# akabeacon_mini_MDBT40.net
KiCad netlist of a schematic drawn in EAGLE
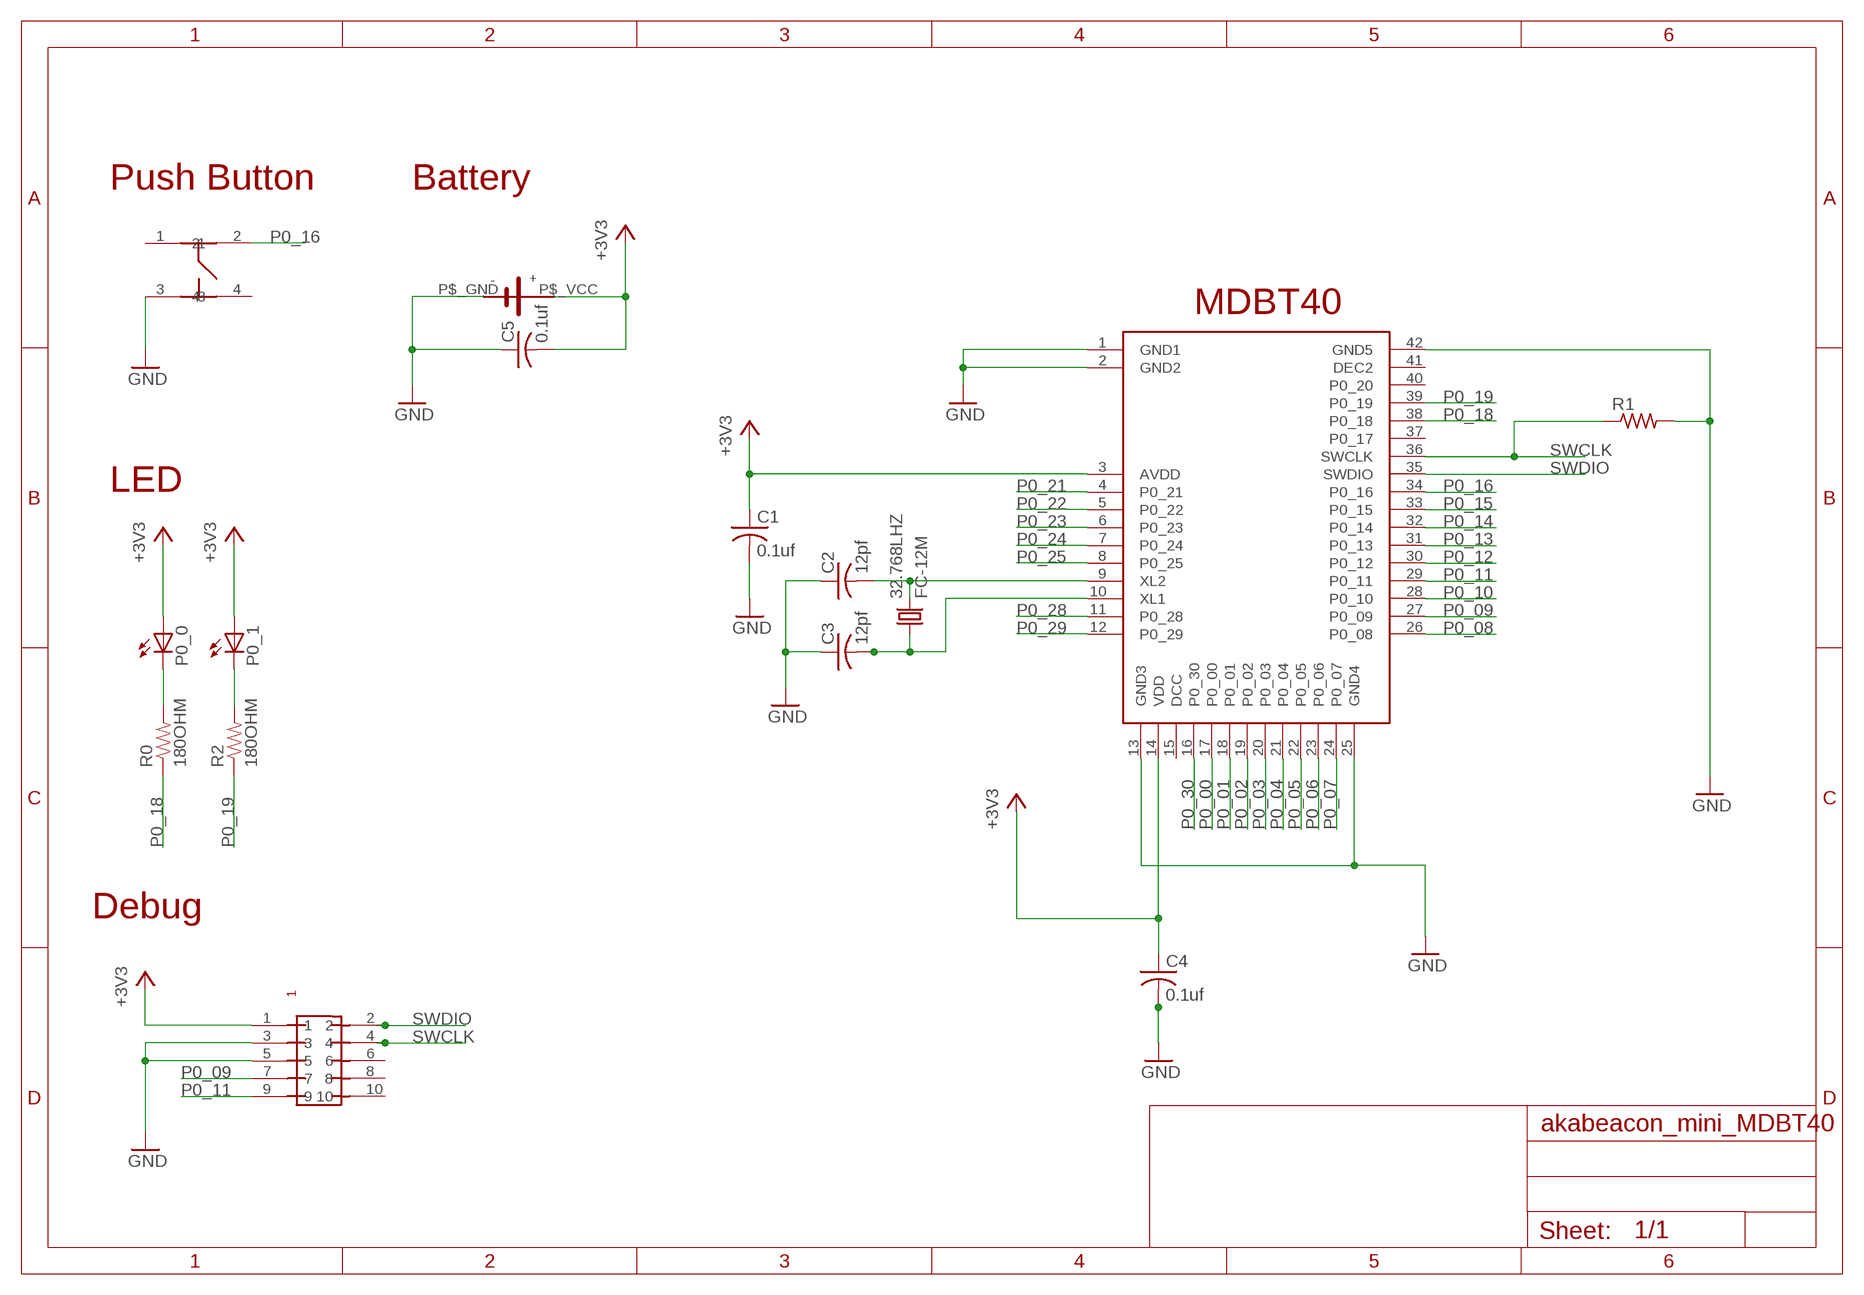
[diagram p0: schematic, sheet 1]

(export (version "E")
  (design (tool "Eeschema 10.0.6"))
  (components
    (comp (ref "32.768LHZ")
      (value "FC-12M")
      (footprint "eagle-import:FC-12M")
      (libsource (lib "eagle-import") (part "FC-12M"))
    )
    (comp (ref "C1")
      (value "0.1uf")
      (footprint "eagle-import:C0603")
      (libsource (lib "eagle-import") (part "C-USC0603"))
    )
    (comp (ref "C2")
      (value "12pf")
      (footprint "eagle-import:C0603")
      (libsource (lib "eagle-import") (part "C-USC0603"))
    )
    (comp (ref "C3")
      (value "12pf")
      (footprint "eagle-import:C0603")
      (libsource (lib "eagle-import") (part "C-USC0603"))
    )
    (comp (ref "C4")
      (value "0.1uf")
      (footprint "eagle-import:C0603")
      (libsource (lib "eagle-import") (part "C-USC0603"))
    )
    (comp (ref "C5")
      (value "0.1uf")
      (footprint "eagle-import:C0603")
      (libsource (lib "eagle-import") (part "C-USC0603"))
    )
    (comp (ref "P0_0")
      (value "LEDCHIP-LED0603")
      (footprint "eagle-import:CHIP-LED0603")
      (libsource (lib "eagle-import") (part "LEDCHIP-LED0603"))
    )
    (comp (ref "P0_1")
      (value "LEDCHIP-LED0603")
      (footprint "eagle-import:CHIP-LED0603")
      (libsource (lib "eagle-import") (part "LEDCHIP-LED0603"))
    )
    (comp (ref "R0")
      (value "180OHM")
      (footprint "eagle-import:0603-RES")
      (libsource (lib "eagle-import") (part "RESISTOR0603-RES"))
    )
    (comp (ref "R1")
      (value "R-US_R0603")
      (footprint "eagle-import:R0603")
      (libsource (lib "eagle-import") (part "R-US_R0603"))
    )
    (comp (ref "R2")
      (value "180OHM")
      (footprint "eagle-import:0603-RES")
      (libsource (lib "eagle-import") (part "RESISTOR0603-RES"))
    )
    (comp (ref "U$1")
      (value "RAYTAC-MDBT40")
      (footprint "eagle-import:RAYTAC-MDBT40")
      (libsource (lib "eagle-import") (part "RAYTAC-MDBT40"))
    )
    (comp (ref "U$2")
      (value "PIN-HEADER-SMT(1.27MM)2X5")
      (footprint "eagle-import:PIN-HEADER-SMT(1.27MM)2X5")
      (libsource (lib "eagle-import") (part "PIN-HEADER-SMT(1.27MM)2X5"))
    )
    (comp (ref "U$3")
      (value "SMTU2450-BOTTOM-MINI")
      (footprint "eagle-import:SMTU2450-BOTTOM-MINI")
      (libsource (lib "eagle-import") (part "SMTU2450-BOTTOM-MINI"))
    )
    (comp (ref "U$5")
      (value "SWICTH-4P(KMR2)")
      (footprint "eagle-import:SWITCH-4P(KMR2)")
      (libsource (lib "eagle-import") (part "SWICTH-4P(KMR2)"))
    )
  )
  (nets
    (net (code "1") (name "+3V3") (class "Default")
      (node (ref "C1") (pin "1") (pinfunction "1_1") (pintype "passive"))
      (node (ref "C4") (pin "1") (pinfunction "1_1") (pintype "passive"))
      (node (ref "C5") (pin "2") (pinfunction "2_2") (pintype "passive"))
      (node (ref "P0_0") (pin "A") (pinfunction "A_A") (pintype "passive"))
      (node (ref "P0_1") (pin "A") (pinfunction "A_A") (pintype "passive"))
      (node (ref "U$1") (pin "14") (pinfunction "VDD_14") (pintype "bidirectional"))
      (node (ref "U$1") (pin "3") (pinfunction "AVDD_3") (pintype "bidirectional"))
      (node (ref "U$2") (pin "1") (pinfunction "1_1") (pintype "bidirectional"))
      (node (ref "U$3") (pin "P$_VCC") (pinfunction "P$_VCC_P$_VCC") (pintype "bidirectional"))
    )
    (net (code "2") (name "/P0_00") (class "Default")
      (node (ref "U$1") (pin "17") (pinfunction "P0_00_17") (pintype "bidirectional"))
    )
    (net (code "3") (name "/P0_01") (class "Default")
      (node (ref "U$1") (pin "18") (pinfunction "P0_01_18") (pintype "bidirectional"))
    )
    (net (code "4") (name "/P0_02") (class "Default")
      (node (ref "U$1") (pin "19") (pinfunction "P0_02_19") (pintype "bidirectional"))
    )
    (net (code "5") (name "/P0_03") (class "Default")
      (node (ref "U$1") (pin "20") (pinfunction "P0_03_20") (pintype "bidirectional"))
    )
    (net (code "6") (name "/P0_04") (class "Default")
      (node (ref "U$1") (pin "21") (pinfunction "P0_04_21") (pintype "bidirectional"))
    )
    (net (code "7") (name "/P0_05") (class "Default")
      (node (ref "U$1") (pin "22") (pinfunction "P0_05_22") (pintype "bidirectional"))
    )
    (net (code "8") (name "/P0_06") (class "Default")
      (node (ref "U$1") (pin "23") (pinfunction "P0_06_23") (pintype "bidirectional"))
    )
    (net (code "9") (name "/P0_07") (class "Default")
      (node (ref "U$1") (pin "24") (pinfunction "P0_07_24") (pintype "bidirectional"))
    )
    (net (code "10") (name "/P0_08") (class "Default")
      (node (ref "U$1") (pin "26") (pinfunction "P0_08_26") (pintype "bidirectional"))
    )
    (net (code "11") (name "/P0_09") (class "Default")
      (node (ref "U$1") (pin "27") (pinfunction "P0_09_27") (pintype "bidirectional"))
      (node (ref "U$2") (pin "7") (pinfunction "7_7") (pintype "bidirectional"))
    )
    (net (code "12") (name "/P0_10") (class "Default")
      (node (ref "U$1") (pin "28") (pinfunction "P0_10_28") (pintype "bidirectional"))
    )
    (net (code "13") (name "/P0_11") (class "Default")
      (node (ref "U$1") (pin "29") (pinfunction "P0_11_29") (pintype "bidirectional"))
      (node (ref "U$2") (pin "9") (pinfunction "9_9") (pintype "bidirectional"))
    )
    (net (code "14") (name "/P0_12") (class "Default")
      (node (ref "U$1") (pin "30") (pinfunction "P0_12_30") (pintype "bidirectional"))
    )
    (net (code "15") (name "/P0_13") (class "Default")
      (node (ref "U$1") (pin "31") (pinfunction "P0_13_31") (pintype "bidirectional"))
    )
    (net (code "16") (name "/P0_14") (class "Default")
      (node (ref "U$1") (pin "32") (pinfunction "P0_14_32") (pintype "bidirectional"))
    )
    (net (code "17") (name "/P0_15") (class "Default")
      (node (ref "U$1") (pin "33") (pinfunction "P0_15_33") (pintype "bidirectional"))
    )
    (net (code "18") (name "/P0_16") (class "Default")
      (node (ref "U$1") (pin "34") (pinfunction "P0_16_34") (pintype "bidirectional"))
      (node (ref "U$5") (pin "2") (pinfunction "2_2") (pintype "bidirectional"))
    )
    (net (code "19") (name "/P0_18") (class "Default")
      (node (ref "R0") (pin "1") (pinfunction "1_1") (pintype "passive"))
      (node (ref "U$1") (pin "38") (pinfunction "P0_18_38") (pintype "bidirectional"))
    )
    (net (code "20") (name "/P0_19") (class "Default")
      (node (ref "R2") (pin "1") (pinfunction "1_1") (pintype "passive"))
      (node (ref "U$1") (pin "39") (pinfunction "P0_19_39") (pintype "bidirectional"))
    )
    (net (code "21") (name "/P0_21") (class "Default")
      (node (ref "U$1") (pin "4") (pinfunction "P0_21_4") (pintype "bidirectional"))
    )
    (net (code "22") (name "/P0_22") (class "Default")
      (node (ref "U$1") (pin "5") (pinfunction "P0_22_5") (pintype "bidirectional"))
    )
    (net (code "23") (name "/P0_23") (class "Default")
      (node (ref "U$1") (pin "6") (pinfunction "P0_23_6") (pintype "bidirectional"))
    )
    (net (code "24") (name "/P0_24") (class "Default")
      (node (ref "U$1") (pin "7") (pinfunction "P0_24_7") (pintype "bidirectional"))
    )
    (net (code "25") (name "/P0_25") (class "Default")
      (node (ref "U$1") (pin "8") (pinfunction "P0_25_8") (pintype "bidirectional"))
    )
    (net (code "26") (name "/P0_28") (class "Default")
      (node (ref "U$1") (pin "11") (pinfunction "P0_28_11") (pintype "bidirectional"))
    )
    (net (code "27") (name "/P0_29") (class "Default")
      (node (ref "U$1") (pin "12") (pinfunction "P0_29_12") (pintype "bidirectional"))
    )
    (net (code "28") (name "/P0_30") (class "Default")
      (node (ref "U$1") (pin "16") (pinfunction "P0_30_16") (pintype "bidirectional"))
    )
    (net (code "29") (name "/SWCLK") (class "Default")
      (node (ref "R1") (pin "1") (pinfunction "1_1") (pintype "passive"))
      (node (ref "U$1") (pin "36") (pinfunction "SWCLK_36") (pintype "bidirectional"))
      (node (ref "U$2") (pin "4") (pinfunction "4_4") (pintype "bidirectional"))
    )
    (net (code "30") (name "/SWDIO") (class "Default")
      (node (ref "U$1") (pin "35") (pinfunction "SWDIO_35") (pintype "bidirectional"))
      (node (ref "U$2") (pin "2") (pinfunction "2_2") (pintype "bidirectional"))
    )
    (net (code "31") (name "GND") (class "Default")
      (node (ref "C1") (pin "2") (pinfunction "2_2") (pintype "passive"))
      (node (ref "C2") (pin "1") (pinfunction "1_1") (pintype "passive"))
      (node (ref "C3") (pin "1") (pinfunction "1_1") (pintype "passive"))
      (node (ref "C4") (pin "2") (pinfunction "2_2") (pintype "passive"))
      (node (ref "C5") (pin "1") (pinfunction "1_1") (pintype "passive"))
      (node (ref "R1") (pin "2") (pinfunction "2_2") (pintype "passive"))
      (node (ref "U$1") (pin "1") (pinfunction "GND1_1") (pintype "bidirectional"))
      (node (ref "U$1") (pin "13") (pinfunction "GND3_13") (pintype "bidirectional"))
      (node (ref "U$1") (pin "2") (pinfunction "GND2_2") (pintype "bidirectional"))
      (node (ref "U$1") (pin "25") (pinfunction "GND4_25") (pintype "bidirectional"))
      (node (ref "U$1") (pin "42") (pinfunction "GND5_42") (pintype "bidirectional"))
      (node (ref "U$2") (pin "3") (pinfunction "3_3") (pintype "bidirectional"))
      (node (ref "U$2") (pin "5") (pinfunction "5_5") (pintype "bidirectional"))
      (node (ref "U$3") (pin "P$_GND") (pinfunction "P$_GND_P$_GND") (pintype "bidirectional"))
      (node (ref "U$5") (pin "3") (pinfunction "3_3") (pintype "bidirectional"))
    )
    (net (code "32") (name "Net-(P0_0-PadC)") (class "Default")
      (node (ref "P0_0") (pin "C") (pinfunction "C_C") (pintype "passive"))
      (node (ref "R0") (pin "2") (pinfunction "2_2") (pintype "passive"))
    )
    (net (code "33") (name "Net-(P0_1-PadC)") (class "Default")
      (node (ref "P0_1") (pin "C") (pinfunction "C_C") (pintype "passive"))
      (node (ref "R2") (pin "2") (pinfunction "2_2") (pintype "passive"))
    )
    (net (code "34") (name "Net-(U$1-XL1)") (class "Default")
      (node (ref "32.768LHZ") (pin "1") (pinfunction "1_1") (pintype "passive"))
      (node (ref "C3") (pin "2") (pinfunction "2_2") (pintype "passive"))
      (node (ref "U$1") (pin "10") (pinfunction "XL1_10") (pintype "bidirectional"))
    )
    (net (code "35") (name "Net-(U$1-XL2)") (class "Default")
      (node (ref "32.768LHZ") (pin "2") (pinfunction "2_2") (pintype "passive"))
      (node (ref "C2") (pin "2") (pinfunction "2_2") (pintype "passive"))
      (node (ref "U$1") (pin "9") (pinfunction "XL2_9") (pintype "bidirectional"))
    )
    (net (code "36") (name "unconnected-(U$1-DCC-Pad15)") (class "Default")
      (node (ref "U$1") (pin "15") (pinfunction "DCC_15") (pintype "bidirectional"))
    )
    (net (code "37") (name "unconnected-(U$1-DEC2-Pad41)") (class "Default")
      (node (ref "U$1") (pin "41") (pinfunction "DEC2_41") (pintype "bidirectional"))
    )
    (net (code "38") (name "unconnected-(U$1-P0_17-Pad37)") (class "Default")
      (node (ref "U$1") (pin "37") (pinfunction "P0_17_37") (pintype "bidirectional"))
    )
    (net (code "39") (name "unconnected-(U$1-P0_20-Pad40)") (class "Default")
      (node (ref "U$1") (pin "40") (pinfunction "P0_20_40") (pintype "bidirectional"))
    )
    (net (code "40") (name "unconnected-(U$2-Pad6)") (class "Default")
      (node (ref "U$2") (pin "6") (pinfunction "6_6") (pintype "bidirectional"))
    )
    (net (code "41") (name "unconnected-(U$2-Pad8)") (class "Default")
      (node (ref "U$2") (pin "8") (pinfunction "8_8") (pintype "bidirectional"))
    )
    (net (code "42") (name "unconnected-(U$2-Pad10)") (class "Default")
      (node (ref "U$2") (pin "10") (pinfunction "10_10") (pintype "bidirectional"))
    )
    (net (code "43") (name "unconnected-(U$5-Pad1)") (class "Default")
      (node (ref "U$5") (pin "1") (pinfunction "1_1") (pintype "bidirectional"))
    )
    (net (code "44") (name "unconnected-(U$5-Pad4)") (class "Default")
      (node (ref "U$5") (pin "4") (pinfunction "4_4") (pintype "bidirectional"))
    )
  )
)
